# Sheet2.net
KiCad netlist of a schematic drawn in Altium Designer
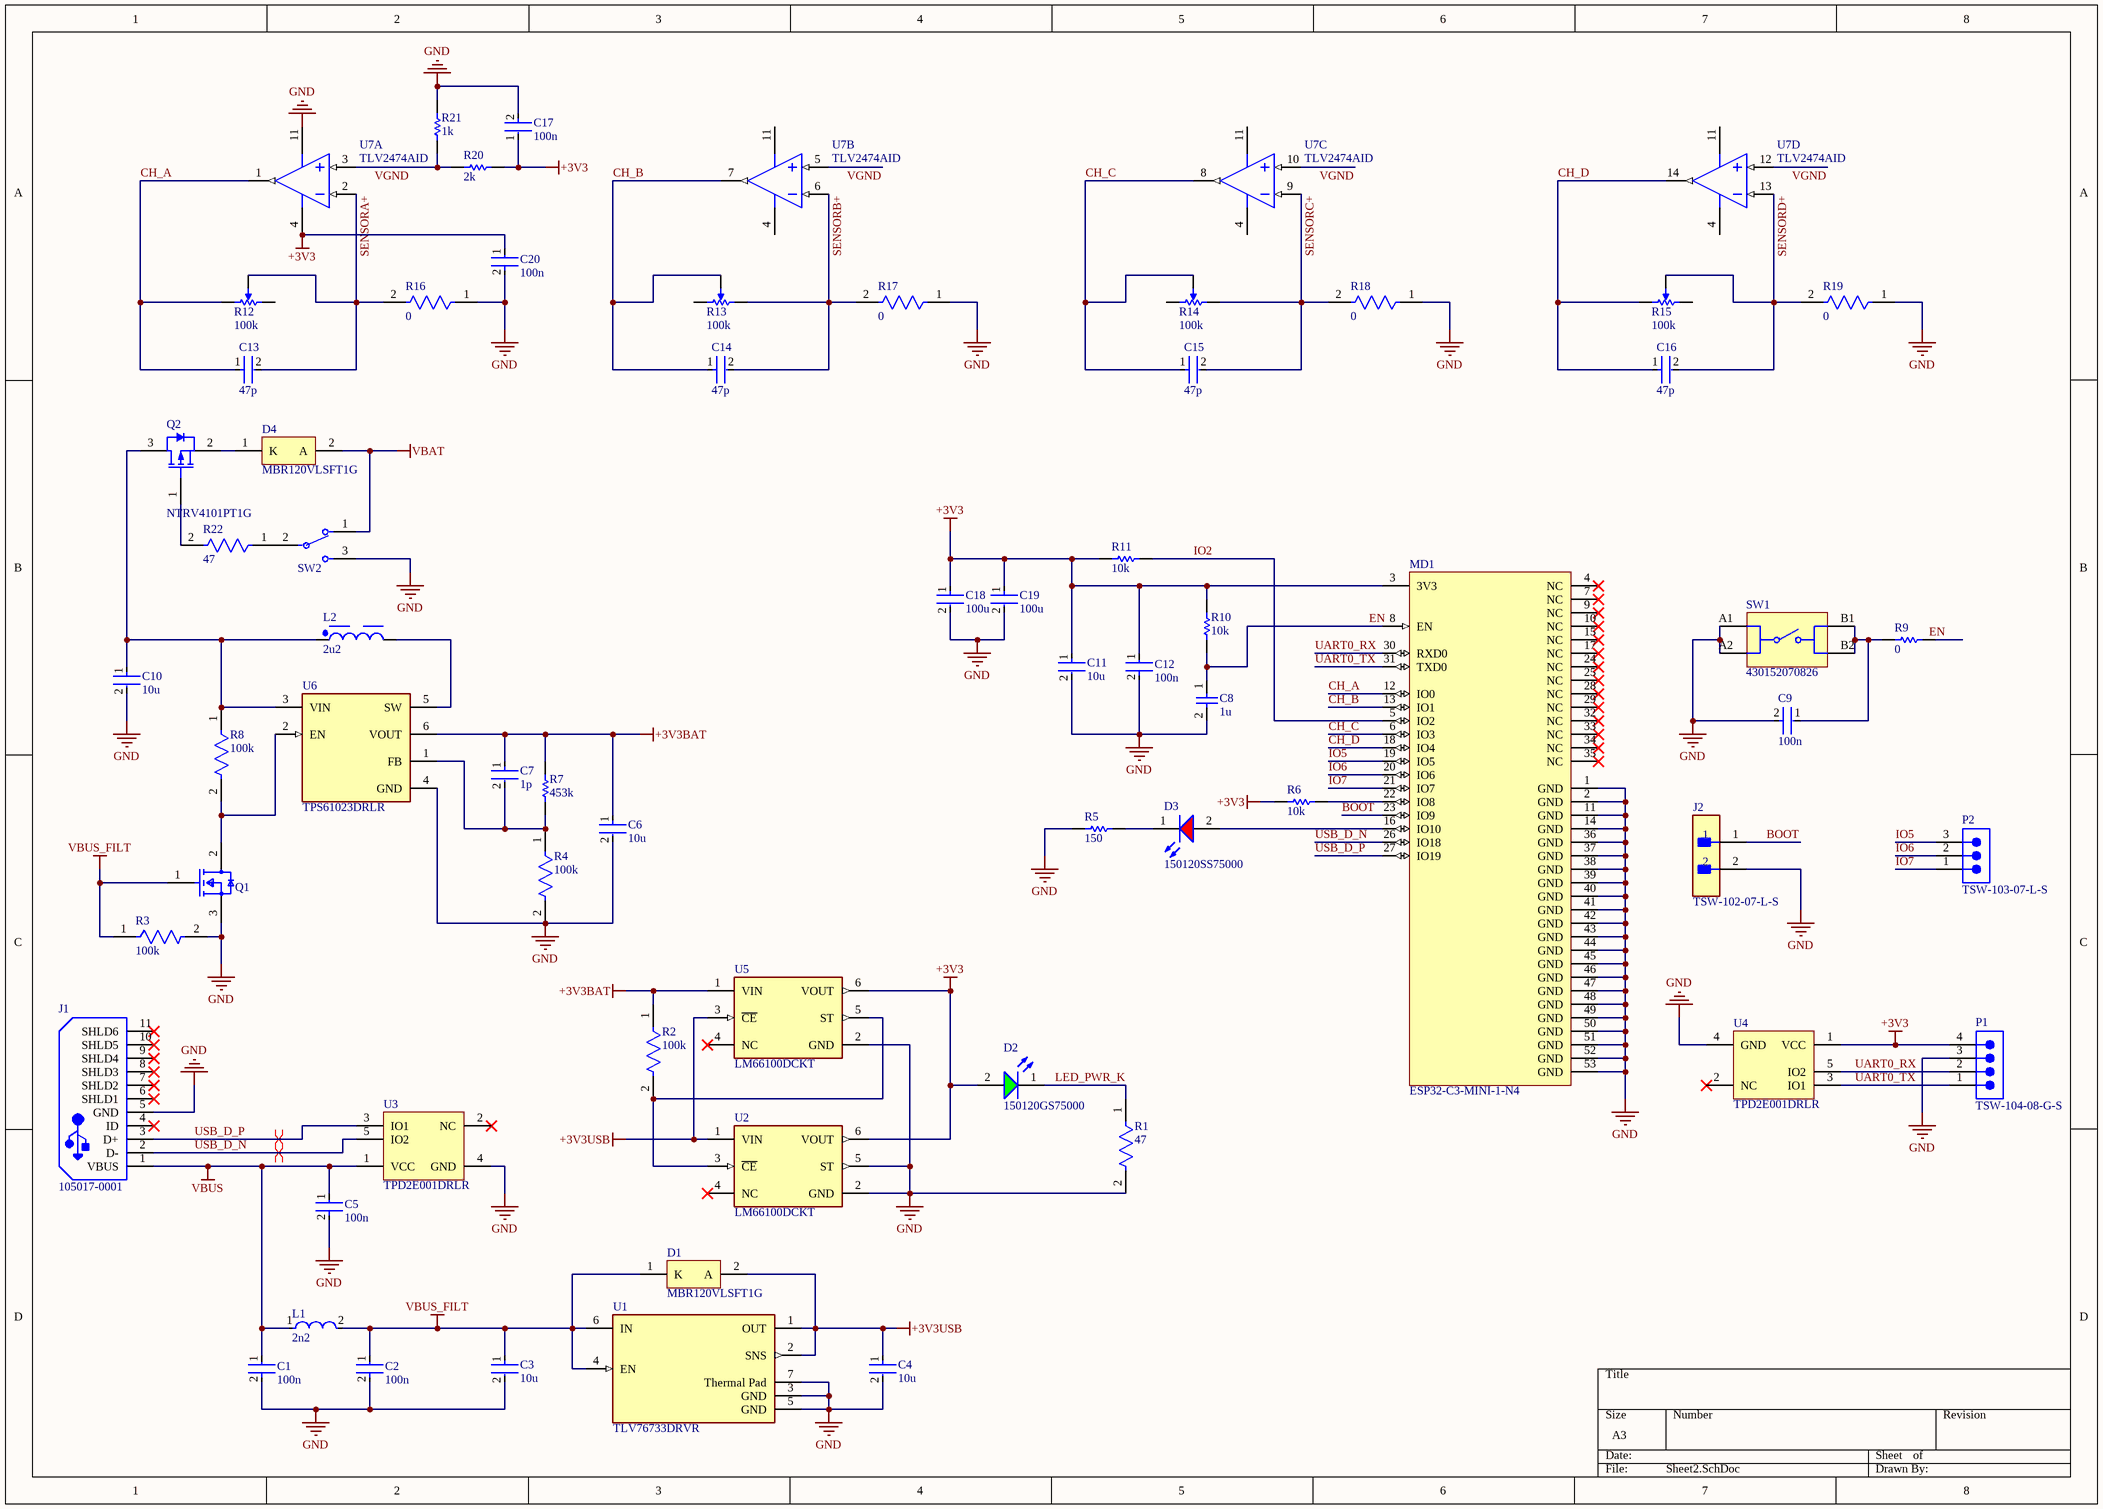
[diagram p0: Sheet2.SchDoc]

(export (version "E")
  (design (tool "Eeschema 10.0.6"))
  (components
    (comp (ref "C1")
      (value "100n")
      (footprint "FP-GRM15-MFG")
      (description "CAP CER 0.1UF 16V X7R 0402")
      (fields (field (name "MANUFACTURER PART NUMBER") "GRM155R71C104KA88D") (field (name "TOLERANCE") "10%"))
      (libsource (lib "Altium Content Vault") (part "236180d848d6139a670b325ea6854c9"))
    )
    (comp (ref "C2")
      (value "100n")
      (footprint "FP-GRM15-MFG")
      (description "CAP CER 0.1UF 16V X7R 0402")
      (fields (field (name "MANUFACTURER PART NUMBER") "GRM155R71C104KA88D") (field (name "TOLERANCE") "10%"))
      (libsource (lib "Altium Content Vault") (part "236180d848d6139a670b325ea6854c9"))
    )
    (comp (ref "C3")
      (value "10u")
      (footprint "FP-CL21-IPC_C")
      (description "CL21 Series 0805 10uF 10V ±20% Tolerance X5R Multilayer Ceramic Chip Capacitor")
      (fields (field (name "TOLERANCE") "20%"))
      (libsource (lib "Altium Content Vault") (part "b4654b650e69147ec39a6b967a45e02"))
    )
    (comp (ref "C4")
      (value "10u")
      (footprint "FP-CL21-IPC_C")
      (description "CL21 Series 0805 10uF 10V ±20% Tolerance X5R Multilayer Ceramic Chip Capacitor")
      (fields (field (name "TOLERANCE") "20%"))
      (libsource (lib "Altium Content Vault") (part "b4654b650e69147ec39a6b967a45e02"))
    )
    (comp (ref "C5")
      (value "100n")
      (footprint "FP-GRM15-MFG")
      (description "CAP CER 0.1UF 16V X7R 0402")
      (fields (field (name "MANUFACTURER PART NUMBER") "GRM155R71C104KA88D") (field (name "TOLERANCE") "10%"))
      (libsource (lib "Altium Content Vault") (part "236180d848d6139a670b325ea6854c9"))
    )
    (comp (ref "C6")
      (value "10u")
      (footprint "FP-CL21-IPC_C")
      (description "CL21 Series 0805 10uF 10V ±20% Tolerance X5R Multilayer Ceramic Chip Capacitor")
      (fields (field (name "TOLERANCE") "20%"))
      (libsource (lib "Altium Content Vault") (part "b4654b650e69147ec39a6b967a45e02"))
    )
    (comp (ref "C7")
      (value "1p")
      (footprint "FP-GJM155-0_05-IPC_B")
      (description "Multi-Layer Ceramic Capacitor 1pF C0G  ±0.1pF 0402 Paper T/R")
      (fields (field (name "VOLTAGE") "50V"))
      (libsource (lib "Altium Content Vault") (part "02cd4be3c70576c341d710602a673aa"))
    )
    (comp (ref "C8")
      (value "1u")
      (footprint "CAPC2013X135X45LL10T25")
      (fields (field (name "MANUFACTURER") "Murata") (field (name "PART NUMBER") "GRM21BR71C105KA01K"))
      (libsource (lib "Altium Content Vault") (part "CAP"))
    )
    (comp (ref "C9")
      (value "100n")
      (footprint "FP-GRM15-MFG")
      (description "CAP CER 0.1UF 16V X7R 0402")
      (fields (field (name "MANUFACTURER PART NUMBER") "GRM155R71C104KA88D") (field (name "TOLERANCE") "10%"))
      (libsource (lib "Altium Content Vault") (part "236180d848d6139a670b325ea6854c9"))
    )
    (comp (ref "C10")
      (value "10u")
      (footprint "FP-GRM21B-0_1-IPC_C")
      (description "Chip Multilayer Ceramic Capacitors for General Purpose, 0805, 10uF, X5R, 15%, 10%, 16V")
      (fields (field (name "TOLERANCE") "10%") (field (name "VOLTAGE") "16V"))
      (libsource (lib "Altium Content Vault") (part "b4654b650e69147ec39a6b967a45e02"))
    )
    (comp (ref "C11")
      (value "10u")
      (footprint "FP-GRM21B-0_1-IPC_C")
      (description "Chip Multilayer Ceramic Capacitors for General Purpose, 0805, 10uF, X5R, 15%, 10%, 16V")
      (fields (field (name "TOLERANCE") "10%") (field (name "VOLTAGE") "16V"))
      (libsource (lib "Altium Content Vault") (part "b4654b650e69147ec39a6b967a45e02"))
    )
    (comp (ref "C12")
      (value "100n")
      (footprint "FP-GRM15-MFG")
      (description "CAP CER 0.1UF 16V X7R 0402")
      (fields (field (name "MANUFACTURER PART NUMBER") "GRM155R71C104KA88D") (field (name "TOLERANCE") "10%"))
      (libsource (lib "Altium Content Vault") (part "236180d848d6139a670b325ea6854c9"))
    )
    (comp (ref "C13")
      (value "47p")
      (footprint "FP-C0805C-DN-MFG")
      (description "CAP CER 47PF 50V C0G/NP0 0805")
      (fields
        (field (name "MANUFACTURER") "KEMET")
        (field (name "MANUFACTURER PART NUMBER") "C0805C470J5GACTU")
      )
      (libsource (lib "Altium Content Vault") (part "b4654b650e69147ec39a6b967a45e02"))
    )
    (comp (ref "C14")
      (value "47p")
      (footprint "FP-C0805C-DN-MFG")
      (description "CAP CER 47PF 50V C0G/NP0 0805")
      (fields
        (field (name "MANUFACTURER") "KEMET")
        (field (name "MANUFACTURER PART NUMBER") "C0805C470J5GACTU")
      )
      (libsource (lib "Altium Content Vault") (part "b4654b650e69147ec39a6b967a45e02"))
    )
    (comp (ref "C15")
      (value "47p")
      (footprint "FP-C0805C-DN-MFG")
      (description "CAP CER 47PF 50V C0G/NP0 0805")
      (fields
        (field (name "MANUFACTURER") "KEMET")
        (field (name "MANUFACTURER PART NUMBER") "C0805C470J5GACTU")
      )
      (libsource (lib "Altium Content Vault") (part "b4654b650e69147ec39a6b967a45e02"))
    )
    (comp (ref "C16")
      (value "47p")
      (footprint "FP-C0805C-DN-MFG")
      (description "CAP CER 47PF 50V C0G/NP0 0805")
      (fields
        (field (name "MANUFACTURER") "KEMET")
        (field (name "MANUFACTURER PART NUMBER") "C0805C470J5GACTU")
      )
      (libsource (lib "Altium Content Vault") (part "b4654b650e69147ec39a6b967a45e02"))
    )
    (comp (ref "C17")
      (value "100n")
      (footprint "FP-GRM15-MFG")
      (description "CAP CER 0.1UF 16V X7R 0402")
      (fields (field (name "MANUFACTURER PART NUMBER") "GRM155R71C104KA88D") (field (name "TOLERANCE") "10%"))
      (libsource (lib "Altium Content Vault") (part "236180d848d6139a670b325ea6854c9"))
    )
    (comp (ref "C18")
      (value "100u")
      (footprint "FP-CL32-IPC_C")
      (description "Cap Ceramic 100uF 10V X5R ±20% SMD 1210 +85°C Embossed T/R")
      (fields (field (name "VOLTAGE") "10V") (field (name "TOLERANCE") "20%"))
      (libsource (lib "Altium Content Vault") (part "b4654b650e69147ec39a6b967a45e02"))
    )
    (comp (ref "C19")
      (value "100u")
      (footprint "FP-CL32-IPC_C")
      (description "Cap Ceramic 100uF 10V X5R ±20% SMD 1210 +85°C Embossed T/R")
      (fields (field (name "VOLTAGE") "10V") (field (name "TOLERANCE") "20%"))
      (libsource (lib "Altium Content Vault") (part "b4654b650e69147ec39a6b967a45e02"))
    )
    (comp (ref "C20")
      (value "100n")
      (footprint "FP-GRM15-MFG")
      (description "CAP CER 0.1UF 16V X7R 0402")
      (fields (field (name "MANUFACTURER PART NUMBER") "GRM155R71C104KA88D") (field (name "TOLERANCE") "10%"))
      (libsource (lib "Altium Content Vault") (part "236180d848d6139a670b325ea6854c9"))
    )
    (comp (ref "D1")
      (value "MBR120VLSFT1G")
      (footprint "ONSC-SOD-123FL-2-498-01_V")
      (description "Schottky Power Rectifier, 2-Pin SOD-123, Pb-Free, Tape and Reel")
      (fields (field (name "MANUFACTURER") "On Semiconductor"))
      (libsource (lib "Altium Content Vault") (part "ONSC-D-K1A2-2_A"))
    )
    (comp (ref "D2")
      (value "150120GS75000")
      (footprint "WL-SMCW_1206_150120xx75000")
      (description "WL-SMCW SMT Mono-Color Chip LED Waterclear")
      (libsource (lib "Altium Content Vault") (part "LED_Green_2A-1K"))
    )
    (comp (ref "D3")
      (value "150120SS75000")
      (footprint "WL-SMCW_1206_150120xx75000")
      (description "Led, Red, 630 Nm, 1.9 V, 30 Ma, 60 Mcd Rohs Compliant: Yes")
      (libsource (lib "Altium Content Vault") (part "LED_Red_2A-1K"))
    )
    (comp (ref "D4")
      (value "MBR120VLSFT1G")
      (footprint "ONSC-SOD-123FL-2-498-01_V")
      (description "Schottky Power Rectifier, 2-Pin SOD-123, Pb-Free, Tape and Reel")
      (fields (field (name "MANUFACTURER") "On Semiconductor"))
      (libsource (lib "Altium Content Vault") (part "ONSC-D-K1A2-2_A"))
    )
    (comp (ref "J1")
      (value "105017-0001")
      (footprint "USB-MICRO-B_V")
      (fields (field (name "MANUFACTURER") "Molex"))
      (libsource (lib "Altium Content Vault") (part "USB-5-6SHLD"))
    )
    (comp (ref "J2")
      (value "TSW-102-07-L-S")
      (footprint "FP-TSW-102-07-L-S-MFG")
      (description "CONN HEADER VERT 2POS 2.54MM")
      (libsource (lib "Altium Content Vault") (part "3bc925449376181038e59eaffc5286c"))
    )
    (comp (ref "L1")
      (value "2n2")
      (footprint "FP-LQW15AN_80-MFG")
      (description "Wire Wound RF Inductor 2.2nH ±0.1nH 2530mA 0.022Ω 0402 (1005)")
      (libsource (lib "Altium Content Vault") (part "725321dda6339637d4d059423bc1c3c"))
    )
    (comp (ref "L2")
      (value "2u2")
      (footprint "WE-PD_7332R")
      (fields (field (name "TOLERANCE") "20%"))
      (libsource (lib "Altium Content Vault") (part "Inductor - 2"))
    )
    (comp (ref "MD1")
      (value "ESP32-C3-MINI-1-N4")
      (footprint "FP-ESP32-C3-MINI-1-N4-MFG")
      (description "Multiprotocol Modules SMD module, ESP32-C3FN4, PCB antenna, -40 C +85 C")
      (libsource (lib "Altium Content Vault") (part "ESP32-C3-MINI-1-N4"))
    )
    (comp (ref "P1")
      (value "TSW-104-08-G-S")
      (footprint "SMTC-TSW-104-08-X-S")
      (description "0.025\" SQ Post Header, Through-hole, Vertical, -55 to 125 degC, 2.54 mm Pitch, 4-Pin, Male, RoHS")
      (fields (field (name "MANUFACTURER") "Samtec"))
      (libsource (lib "Altium Content Vault") (part "SMTC-TSW-104-08-X-S"))
    )
    (comp (ref "P2")
      (value "TSW-103-07-L-S")
      (footprint "SMTC-TSW-103-07-X-S")
      (description "0.025\" SQ Post Header, Through-hole, Vertical, -55 to 125 degC, 2.54 mm Pitch, 3-Pin, Male, RoHS")
      (fields (field (name "MANUFACTURER") "Samtec"))
      (libsource (lib "Altium Content Vault") (part "SMTC-TSW-103-X-X-S-X"))
    )
    (comp (ref "Q1")
      (value "FDN337N")
      (footprint "FP-527AG-MFG")
      (description "MOSFET N-CH 30V 2.2A SSOT3")
      (libsource (lib "Altium Content Vault") (part "b44c8776e10362b01251f5cff19d373"))
    )
    (comp (ref "Q2")
      (value "NTRV4101PT1G")
      (footprint "ONSC-SOT-23-3-318-08_V")
      (description "Trench Power MOSFET, -20 V, Single P-Channel, 3-Pin SOT-23, Pb-Free, Tape and Reel")
      (fields (field (name "MANUFACTURER") "On Semiconductor"))
      (libsource (lib "Altium Content Vault") (part "ONSC-PMOS-G1S2D3-3_D"))
    )
    (comp (ref "R1")
      (value "47")
      (footprint "FP-RC0603-0_55-MFG")
      (fields (field (name "TOLERANCE") "1%"))
      (libsource (lib "Altium Content Vault") (part "1029c3af85768c4190bb7ad29bc67b5"))
    )
    (comp (ref "R2")
      (value "100k")
      (footprint "FP-RC0805-0_6-IPC_C")
      (description "RES 100K OHM 1% 1/8W 0805")
      (fields (field (name "TOLERANCE") "1%"))
      (libsource (lib "Altium Content Vault") (part "1029c3af85768c4190bb7ad29bc67b5"))
    )
    (comp (ref "R3")
      (value "100k")
      (footprint "FP-RC0805-0_6-IPC_C")
      (description "RES 100K OHM 1% 1/8W 0805")
      (fields (field (name "TOLERANCE") "1%"))
      (libsource (lib "Altium Content Vault") (part "1029c3af85768c4190bb7ad29bc67b5"))
    )
    (comp (ref "R4")
      (value "100k")
      (footprint "FP-RC0805-0_6-IPC_C")
      (description "RES 100K OHM 1% 1/8W 0805")
      (fields (field (name "TOLERANCE") "1%"))
      (libsource (lib "Altium Content Vault") (part "1029c3af85768c4190bb7ad29bc67b5"))
    )
    (comp (ref "R5")
      (value "150")
      (footprint "RESC1608X55X25ML10T15")
      (description "Chip Resistor, 150 Ohm, +/- 1%, 0.1 W, -55 to 155 degC, 0603 (1608 Metric), RoHS, Tape and Reel")
      (libsource (lib "Altium Content Vault") (part "RES-2"))
    )
    (comp (ref "R6")
      (value "10k")
      (footprint "RESC2013X60X35NL10T20")
      (description "Chip Resistor, 10 KOhm, +/- 1%, 0.125 W, -55 to 155 degC, 0805 (2012 Metric), RoHS, Tape and Reel")
      (fields (field (name "MANUFACTURER") "Yageo"))
      (libsource (lib "Altium Content Vault") (part "RES-2"))
    )
    (comp (ref "R7")
      (value "453k")
      (footprint "RESC2013X60X35NL10T20")
      (fields (field (name "PART NUMBER") "RC0805FR-07453KL") (field (name "MANUFACTURER") "Yageo"))
      (libsource (lib "Altium Content Vault") (part "RES"))
    )
    (comp (ref "R8")
      (value "100k")
      (footprint "FP-RC0805-0_6-IPC_C")
      (description "RES 100K OHM 1% 1/8W 0805")
      (fields (field (name "TOLERANCE") "1%"))
      (libsource (lib "Altium Content Vault") (part "1029c3af85768c4190bb7ad29bc67b5"))
    )
    (comp (ref "R9")
      (value "0")
      (footprint "RESC2013X60X35ML10T20")
      (fields (field (name "TOLERANCE") "5%") (field (name "MANUFACTURER") "Yageo"))
      (libsource (lib "Altium Content Vault") (part "RES-2"))
    )
    (comp (ref "R10")
      (value "10k")
      (footprint "RESC2013X60X35NL10T20")
      (description "Chip Resistor, 10 KOhm, +/- 1%, 0.125 W, -55 to 155 degC, 0805 (2012 Metric), RoHS, Tape and Reel")
      (fields (field (name "MANUFACTURER") "Yageo"))
      (libsource (lib "Altium Content Vault") (part "RES-2"))
    )
    (comp (ref "R11")
      (value "10k")
      (footprint "RESC2013X60X35NL10T20")
      (description "Chip Resistor, 10 KOhm, +/- 1%, 0.125 W, -55 to 155 degC, 0805 (2012 Metric), RoHS, Tape and Reel")
      (fields (field (name "MANUFACTURER") "Yageo"))
      (libsource (lib "Altium Content Vault") (part "RES-2"))
    )
    (comp (ref "R12")
      (value "100k")
      (footprint "BOUR-3214W_V")
      (fields (field (name "MANUFACTURER") "Bourns"))
      (libsource (lib "Altium Content Vault") (part "RES-ADJ-3_A"))
    )
    (comp (ref "R13")
      (value "100k")
      (footprint "BOUR-3214W_V")
      (fields (field (name "MANUFACTURER") "Bourns"))
      (libsource (lib "Altium Content Vault") (part "RES-ADJ-3_A"))
    )
    (comp (ref "R14")
      (value "100k")
      (footprint "BOUR-3214W_V")
      (fields (field (name "MANUFACTURER") "Bourns"))
      (libsource (lib "Altium Content Vault") (part "RES-ADJ-3_A"))
    )
    (comp (ref "R15")
      (value "100k")
      (footprint "BOUR-3214W_V")
      (fields (field (name "MANUFACTURER") "Bourns"))
      (libsource (lib "Altium Content Vault") (part "RES-ADJ-3_A"))
    )
    (comp (ref "R16")
      (value "0")
      (footprint "FP-RC2512-0_65-IPC_C")
      (description "RES SMD 0 OHM JUMPER 1W 2512")
      (fields (field (name "TOLERANCE") "5%"))
      (libsource (lib "Altium Content Vault") (part "1029c3af85768c4190bb7ad29bc67b5"))
    )
    (comp (ref "R17")
      (value "0")
      (footprint "FP-RC2512-0_65-IPC_C")
      (description "RES SMD 0 OHM JUMPER 1W 2512")
      (fields (field (name "TOLERANCE") "5%"))
      (libsource (lib "Altium Content Vault") (part "1029c3af85768c4190bb7ad29bc67b5"))
    )
    (comp (ref "R18")
      (value "0")
      (footprint "FP-RC2512-0_65-IPC_C")
      (description "RES SMD 0 OHM JUMPER 1W 2512")
      (fields (field (name "TOLERANCE") "5%"))
      (libsource (lib "Altium Content Vault") (part "1029c3af85768c4190bb7ad29bc67b5"))
    )
    (comp (ref "R19")
      (value "0")
      (footprint "FP-RC2512-0_65-IPC_C")
      (description "RES SMD 0 OHM JUMPER 1W 2512")
      (fields (field (name "TOLERANCE") "5%"))
      (libsource (lib "Altium Content Vault") (part "1029c3af85768c4190bb7ad29bc67b5"))
    )
    (comp (ref "R20")
      (value "2k")
      (footprint "RESC2013X60X35ML10T20")
      (fields (field (name "MANUFACTURER") "Yageo") (field (name "PART NUMBER") "RC0805JR-072KL"))
      (libsource (lib "Altium Content Vault") (part "RES"))
    )
    (comp (ref "R21")
      (value "1k")
      (footprint "RESC2013X60X35ML10T20")
      (description "Chip Resistor, 1 KOhm, +/- 1%, 125 mW, -55 to 155 degC, 0805 (2012 Metric), RoHS, Tape and Reel")
      (fields (field (name "TOLERANCE") "1%") (field (name "MANUFACTURER") "Yageo"))
      (libsource (lib "Altium Content Vault") (part "RES-2"))
    )
    (comp (ref "R22")
      (value "47")
      (footprint "FP-RC0603-0_55-MFG")
      (fields (field (name "TOLERANCE") "1%"))
      (libsource (lib "Altium Content Vault") (part "1029c3af85768c4190bb7ad29bc67b5"))
    )
    (comp (ref "SW1")
      (value "430152070826")
      (footprint "430152070826")
      (description "Switch Tactile N.O. SPST Round Button Gull Wing 0.05A 12VDC 500000Cycles 2.55N SMD Reel")
      (libsource (lib "Altium Content Vault") (part "SPST-NO_4P"))
    )
    (comp (ref "SW2")
      (value "JS102011SAQN")
      (footprint "FP-JS102011SAQN-MFG")
      (description "SWITCH SLIDE SPDT 300MA 6V")
      (libsource (lib "Altium Content Vault") (part "39e195cbbadc85d1df0d7eb6847d379"))
    )
    (comp (ref "U1")
      (value "TLV76733DRVR")
      (footprint "FP-DRV0006A-IPC_C")
      (description "VOLTAGE COMPARATOR")
      (libsource (lib "Altium Content Vault") (part "527f072e48108a7b9f646086bfc5874"))
    )
    (comp (ref "U2")
      (value "LM66100DCKT")
      (footprint "FP-DCK0006A-IPC_C")
      (description "IC OR CTRLR IDEAL DIODE SC70-6")
      (libsource (lib "Altium Content Vault") (part "3595dc506fef48fc1df3095330a4feb"))
    )
    (comp (ref "U3")
      (value "TPD2E001DRLR")
      (footprint "DRL0005A_L")
      (fields (field (name "MANUFACTURER") "Texas Instruments"))
      (libsource (lib "") (part "TI-TPD2E001-SOT_DRL-5_1"))
    )
    (comp (ref "U4")
      (value "TPD2E001DRLR")
      (footprint "DRL0005A_L")
      (fields (field (name "MANUFACTURER") "Texas Instruments"))
      (libsource (lib "Altium Content Vault") (part "TI-TPD2E001-SOT_DRL-5"))
    )
    (comp (ref "U5")
      (value "LM66100DCKT")
      (footprint "FP-DCK0006A-IPC_C")
      (description "IC OR CTRLR IDEAL DIODE SC70-6")
      (libsource (lib "Altium Content Vault") (part "3595dc506fef48fc1df3095330a4feb"))
    )
    (comp (ref "U6")
      (value "TPS61023DRLR")
      (footprint "FP-DRL0006A-MFG")
      (description "FINISH GOODS FOR TPS61023")
      (libsource (lib "Altium Content Vault") (part "b28b3e956a4ad07201ce69f9d09f9a8"))
    )
    (comp (ref "U7")
      (value "TLV2474AID")
      (footprint "D0014A_N")
      (fields (field (name "MANUFACTURER") "Texas Instruments"))
      (libsource (lib "Altium Content Vault") (part "TI-TLC_TLV_TLC1079-14"))
    )
  )
  (nets
    (net (code "1") (name "+3V3") (class "Default")
      (node (ref "C11") (pin "1") (pinfunction "1_1") (pintype "passive"))
      (node (ref "C12") (pin "1") (pinfunction "1_1") (pintype "passive"))
      (node (ref "C17") (pin "1") (pinfunction "1_1") (pintype "passive"))
      (node (ref "C18") (pin "1") (pinfunction "1_1") (pintype "passive"))
      (node (ref "C19") (pin "1") (pinfunction "1_1") (pintype "passive"))
      (node (ref "C20") (pin "1") (pinfunction "1_1") (pintype "passive"))
      (node (ref "D2") (pin "2") (pinfunction "A_2") (pintype "passive"))
      (node (ref "MD1") (pin "3") (pinfunction "3V3_3") (pintype "power_in"))
      (node (ref "P1") (pin "4") (pinfunction "4_4") (pintype "passive"))
      (node (ref "R10") (pin "2") (pinfunction "2_2") (pintype "passive"))
      (node (ref "R11") (pin "1") (pinfunction "1_1") (pintype "passive"))
      (node (ref "R20") (pin "2") (pinfunction "2_2") (pintype "passive"))
      (node (ref "R6") (pin "1") (pinfunction "1_1") (pintype "passive"))
      (node (ref "U2") (pin "6") (pinfunction "VOUT_6") (pintype "output"))
      (node (ref "U4") (pin "1") (pinfunction "VCC_1") (pintype "power_in"))
      (node (ref "U5") (pin "6") (pinfunction "VOUT_6") (pintype "output"))
      (node (ref "U7") (pin "4") (pinfunction "VDD_4") (pintype "power_in"))
    )
    (net (code "2") (name "+3V3BAT") (class "Default")
      (node (ref "C6") (pin "1") (pinfunction "1_1") (pintype "passive"))
      (node (ref "C7") (pin "1") (pinfunction "1_1") (pintype "passive"))
      (node (ref "R2") (pin "1") (pinfunction "1_1") (pintype "passive"))
      (node (ref "R7") (pin "2") (pinfunction "2_2") (pintype "passive"))
      (node (ref "U5") (pin "1") (pinfunction "VIN_1") (pintype "power_in"))
      (node (ref "U6") (pin "6") (pinfunction "VOUT_6") (pintype "power_in"))
    )
    (net (code "3") (name "+3V3USB") (class "Default")
      (node (ref "C4") (pin "1") (pinfunction "1_1") (pintype "passive"))
      (node (ref "D1") (pin "2") (pinfunction "A_2") (pintype "passive"))
      (node (ref "U1") (pin "1") (pinfunction "OUT_1") (pintype "passive"))
      (node (ref "U1") (pin "2") (pinfunction "SNS_2") (pintype "output"))
      (node (ref "U2") (pin "1") (pinfunction "VIN_1") (pintype "power_in"))
      (node (ref "U5") (pin "3") (pinfunction "~{CE}_3") (pintype "input"))
    )
    (net (code "4") (name "/BOOT") (class "Default")
      (node (ref "J2") (pin "1") (pinfunction "1_1") (pintype "passive"))
      (node (ref "MD1") (pin "23") (pinfunction "IO9_23") (pintype "bidirectional"))
    )
    (net (code "5") (name "/CH_A") (class "Default")
      (node (ref "C13") (pin "1") (pinfunction "1_1") (pintype "passive"))
      (node (ref "MD1") (pin "12") (pinfunction "IO0_12") (pintype "bidirectional"))
      (node (ref "R12") (pin "3") (pinfunction "3_3") (pintype "passive"))
      (node (ref "U7") (pin "1") (pinfunction "OUT1_1") (pintype "output"))
    )
    (net (code "6") (name "/CH_B") (class "Default")
      (node (ref "C14") (pin "1") (pinfunction "1_1") (pintype "passive"))
      (node (ref "MD1") (pin "13") (pinfunction "IO1_13") (pintype "bidirectional"))
      (node (ref "R13") (pin "2") (pinfunction "2_2") (pintype "passive"))
      (node (ref "U7") (pin "7") (pinfunction "OUT2_7") (pintype "output"))
    )
    (net (code "7") (name "/CH_C") (class "Default")
      (node (ref "C15") (pin "1") (pinfunction "1_1") (pintype "passive"))
      (node (ref "MD1") (pin "6") (pinfunction "IO3_6") (pintype "bidirectional"))
      (node (ref "R14") (pin "2") (pinfunction "2_2") (pintype "passive"))
      (node (ref "U7") (pin "8") (pinfunction "OUT3_8") (pintype "output"))
    )
    (net (code "8") (name "/CH_D") (class "Default")
      (node (ref "C16") (pin "1") (pinfunction "1_1") (pintype "passive"))
      (node (ref "MD1") (pin "18") (pinfunction "IO4_18") (pintype "bidirectional"))
      (node (ref "R15") (pin "3") (pinfunction "3_3") (pintype "passive"))
      (node (ref "U7") (pin "14") (pinfunction "OUT4_14") (pintype "output"))
    )
    (net (code "9") (name "/EN") (class "Default")
      (node (ref "C8") (pin "1") (pinfunction "1_1") (pintype "passive"))
      (node (ref "MD1") (pin "8") (pinfunction "EN_8") (pintype "input"))
      (node (ref "R10") (pin "1") (pinfunction "1_1") (pintype "passive"))
      (node (ref "R9") (pin "2") (pinfunction "2_2") (pintype "passive"))
    )
    (net (code "10") (name "/IO2") (class "Default")
      (node (ref "MD1") (pin "5") (pinfunction "IO2_5") (pintype "bidirectional"))
      (node (ref "R11") (pin "2") (pinfunction "2_2") (pintype "passive"))
    )
    (net (code "11") (name "/IO5") (class "Default")
      (node (ref "MD1") (pin "19") (pinfunction "IO5_19") (pintype "bidirectional"))
      (node (ref "P2") (pin "3") (pinfunction "3_3") (pintype "passive"))
    )
    (net (code "12") (name "/IO6") (class "Default")
      (node (ref "MD1") (pin "20") (pinfunction "IO6_20") (pintype "bidirectional"))
      (node (ref "P2") (pin "2") (pinfunction "2_2") (pintype "passive"))
    )
    (net (code "13") (name "/IO7") (class "Default")
      (node (ref "MD1") (pin "21") (pinfunction "IO7_21") (pintype "bidirectional"))
      (node (ref "P2") (pin "1") (pinfunction "1_1") (pintype "passive"))
    )
    (net (code "14") (name "/LED_PWR_K") (class "Default")
      (node (ref "D2") (pin "1") (pinfunction "K_1") (pintype "passive"))
      (node (ref "R1") (pin "1") (pinfunction "1_1") (pintype "passive"))
    )
    (net (code "15") (name "/SENSORA+") (class "Default")
      (node (ref "C13") (pin "2") (pinfunction "2_2") (pintype "passive"))
      (node (ref "R12") (pin "2") (pinfunction "2_2") (pintype "passive"))
      (node (ref "R16") (pin "2") (pinfunction "2_2") (pintype "passive"))
      (node (ref "U7") (pin "2") (pinfunction "IN1-_2") (pintype "input"))
    )
    (net (code "16") (name "/SENSORB+") (class "Default")
      (node (ref "C14") (pin "2") (pinfunction "2_2") (pintype "passive"))
      (node (ref "R13") (pin "1") (pinfunction "1_1") (pintype "passive"))
      (node (ref "R17") (pin "2") (pinfunction "2_2") (pintype "passive"))
      (node (ref "U7") (pin "6") (pinfunction "IN2-_6") (pintype "input"))
    )
    (net (code "17") (name "/SENSORC+") (class "Default")
      (node (ref "C15") (pin "2") (pinfunction "2_2") (pintype "passive"))
      (node (ref "R14") (pin "1") (pinfunction "1_1") (pintype "passive"))
      (node (ref "R18") (pin "2") (pinfunction "2_2") (pintype "passive"))
      (node (ref "U7") (pin "9") (pinfunction "IN3-_9") (pintype "input"))
    )
    (net (code "18") (name "/SENSORD+") (class "Default")
      (node (ref "C16") (pin "2") (pinfunction "2_2") (pintype "passive"))
      (node (ref "R15") (pin "2") (pinfunction "2_2") (pintype "passive"))
      (node (ref "R19") (pin "2") (pinfunction "2_2") (pintype "passive"))
      (node (ref "U7") (pin "13") (pinfunction "IN4-_13") (pintype "input"))
    )
    (net (code "19") (name "/UART0_RX") (class "Default")
      (node (ref "MD1") (pin "30") (pinfunction "RXD0_30") (pintype "bidirectional"))
      (node (ref "P1") (pin "2") (pinfunction "2_2") (pintype "passive"))
      (node (ref "U4") (pin "5") (pinfunction "IO2_5") (pintype "passive"))
    )
    (net (code "20") (name "/UART0_TX") (class "Default")
      (node (ref "MD1") (pin "31") (pinfunction "TXD0_31") (pintype "bidirectional"))
      (node (ref "P1") (pin "1") (pinfunction "1_1") (pintype "passive"))
      (node (ref "U4") (pin "3") (pinfunction "IO1_3") (pintype "passive"))
    )
    (net (code "21") (name "/USB_D_N") (class "Default")
      (node (ref "J1") (pin "2") (pinfunction "D-_2") (pintype "passive"))
      (node (ref "MD1") (pin "26") (pinfunction "IO18_26") (pintype "bidirectional"))
      (node (ref "U3") (pin "5") (pinfunction "IO2_5") (pintype "passive"))
    )
    (net (code "22") (name "/USB_D_P") (class "Default")
      (node (ref "J1") (pin "3") (pinfunction "D+_3") (pintype "passive"))
      (node (ref "MD1") (pin "27") (pinfunction "IO19_27") (pintype "bidirectional"))
      (node (ref "U3") (pin "3") (pinfunction "IO1_3") (pintype "passive"))
    )
    (net (code "23") (name "/VGND") (class "Default")
      (node (ref "R20") (pin "1") (pinfunction "1_1") (pintype "passive"))
      (node (ref "R21") (pin "1") (pinfunction "1_1") (pintype "passive"))
      (node (ref "U7") (pin "10") (pinfunction "IN3+_10") (pintype "input"))
      (node (ref "U7") (pin "12") (pinfunction "IN4+_12") (pintype "input"))
      (node (ref "U7") (pin "3") (pinfunction "IN1+_3") (pintype "input"))
      (node (ref "U7") (pin "5") (pinfunction "IN2+_5") (pintype "input"))
    )
    (net (code "24") (name "GND") (class "Default")
      (node (ref "C1") (pin "2") (pinfunction "2_2") (pintype "passive"))
      (node (ref "C10") (pin "2") (pinfunction "2_2") (pintype "passive"))
      (node (ref "C11") (pin "2") (pinfunction "2_2") (pintype "passive"))
      (node (ref "C12") (pin "2") (pinfunction "2_2") (pintype "passive"))
      (node (ref "C17") (pin "2") (pinfunction "2_2") (pintype "passive"))
      (node (ref "C18") (pin "2") (pinfunction "2_2") (pintype "passive"))
      (node (ref "C19") (pin "2") (pinfunction "2_2") (pintype "passive"))
      (node (ref "C2") (pin "2") (pinfunction "2_2") (pintype "passive"))
      (node (ref "C20") (pin "2") (pinfunction "2_2") (pintype "passive"))
      (node (ref "C3") (pin "2") (pinfunction "2_2") (pintype "passive"))
      (node (ref "C4") (pin "2") (pinfunction "2_2") (pintype "passive"))
      (node (ref "C5") (pin "2") (pinfunction "2_2") (pintype "passive"))
      (node (ref "C6") (pin "2") (pinfunction "2_2") (pintype "passive"))
      (node (ref "C8") (pin "2") (pinfunction "2_2") (pintype "passive"))
      (node (ref "C9") (pin "2") (pinfunction "2_2") (pintype "passive"))
      (node (ref "J1") (pin "5") (pinfunction "GND_5") (pintype "passive"))
      (node (ref "J2") (pin "2") (pinfunction "2_2") (pintype "passive"))
      (node (ref "MD1") (pin "1") (pinfunction "GND_1") (pintype "power_in"))
      (node (ref "MD1") (pin "11") (pinfunction "GND_11") (pintype "power_in"))
      (node (ref "MD1") (pin "14") (pinfunction "GND_14") (pintype "power_in"))
      (node (ref "MD1") (pin "2") (pinfunction "GND_2") (pintype "power_in"))
      (node (ref "MD1") (pin "36") (pinfunction "GND_36") (pintype "power_in"))
      (node (ref "MD1") (pin "37") (pinfunction "GND_37") (pintype "power_in"))
      (node (ref "MD1") (pin "38") (pinfunction "GND_38") (pintype "power_in"))
      (node (ref "MD1") (pin "39") (pinfunction "GND_39") (pintype "power_in"))
      (node (ref "MD1") (pin "40") (pinfunction "GND_40") (pintype "power_in"))
      (node (ref "MD1") (pin "41") (pinfunction "GND_41") (pintype "power_in"))
      (node (ref "MD1") (pin "42") (pinfunction "GND_42") (pintype "power_in"))
      (node (ref "MD1") (pin "43") (pinfunction "GND_43") (pintype "power_in"))
      (node (ref "MD1") (pin "44") (pinfunction "GND_44") (pintype "power_in"))
      (node (ref "MD1") (pin "45") (pinfunction "GND_45") (pintype "power_in"))
      (node (ref "MD1") (pin "46") (pinfunction "GND_46") (pintype "power_in"))
      (node (ref "MD1") (pin "47") (pinfunction "GND_47") (pintype "power_in"))
      (node (ref "MD1") (pin "48") (pinfunction "GND_48") (pintype "power_in"))
      (node (ref "MD1") (pin "49") (pinfunction "GND_49") (pintype "power_in"))
      (node (ref "MD1") (pin "50") (pinfunction "GND_50") (pintype "power_in"))
      (node (ref "MD1") (pin "51") (pinfunction "GND_51") (pintype "power_in"))
      (node (ref "MD1") (pin "52") (pinfunction "GND_52") (pintype "power_in"))
      (node (ref "MD1") (pin "53") (pinfunction "GND_53") (pintype "power_in"))
      (node (ref "P1") (pin "3") (pinfunction "3_3") (pintype "passive"))
      (node (ref "Q1") (pin "3") (pinfunction "S_3") (pintype "passive"))
      (node (ref "R1") (pin "2") (pinfunction "2_2") (pintype "passive"))
      (node (ref "R16") (pin "1") (pinfunction "1_1") (pintype "passive"))
      (node (ref "R17") (pin "1") (pinfunction "1_1") (pintype "passive"))
      (node (ref "R18") (pin "1") (pinfunction "1_1") (pintype "passive"))
      (node (ref "R19") (pin "1") (pinfunction "1_1") (pintype "passive"))
      (node (ref "R21") (pin "2") (pinfunction "2_2") (pintype "passive"))
      (node (ref "R3") (pin "2") (pinfunction "2_2") (pintype "passive"))
      (node (ref "R4") (pin "2") (pinfunction "2_2") (pintype "passive"))
      (node (ref "R5") (pin "1") (pinfunction "1_1") (pintype "passive"))
      (node (ref "SW1") (pin "A1") (pinfunction "A1_A1") (pintype "passive"))
      (node (ref "SW1") (pin "A2") (pinfunction "A2_A2") (pintype "passive"))
      (node (ref "SW2") (pin "3") (pinfunction "3_3") (pintype "passive"))
      (node (ref "U1") (pin "3") (pinfunction "GND_3") (pintype "power_in"))
      (node (ref "U1") (pin "5") (pinfunction "GND_5") (pintype "power_in"))
      (node (ref "U1") (pin "7") (pinfunction "Thermal_Pad_7") (pintype "passive"))
      (node (ref "U2") (pin "2") (pinfunction "GND_2") (pintype "power_in"))
      (node (ref "U2") (pin "5") (pinfunction "ST_5") (pintype "output"))
      (node (ref "U3") (pin "4") (pinfunction "GND_4") (pintype "power_in"))
      (node (ref "U4") (pin "4") (pinfunction "GND_4") (pintype "power_in"))
      (node (ref "U5") (pin "2") (pinfunction "GND_2") (pintype "power_in"))
      (node (ref "U6") (pin "4") (pinfunction "GND_4") (pintype "power_in"))
      (node (ref "U7") (pin "11") (pinfunction "GND_11") (pintype "power_in"))
    )
    (net (code "25") (name "Net-(C9-Pad1)") (class "Default")
      (node (ref "C9") (pin "1") (pinfunction "1_1") (pintype "passive"))
      (node (ref "R9") (pin "1") (pinfunction "1_1") (pintype "passive"))
      (node (ref "SW1") (pin "B1") (pinfunction "B1_B1") (pintype "passive"))
      (node (ref "SW1") (pin "B2") (pinfunction "B2_B2") (pintype "passive"))
    )
    (net (code "26") (name "Net-(D3-A)") (class "Default")
      (node (ref "D3") (pin "2") (pinfunction "A_2") (pintype "passive"))
      (node (ref "MD1") (pin "16") (pinfunction "IO10_16") (pintype "bidirectional"))
    )
    (net (code "27") (name "Net-(D3-K)") (class "Default")
      (node (ref "D3") (pin "1") (pinfunction "K_1") (pintype "passive"))
      (node (ref "R5") (pin "2") (pinfunction "2_2") (pintype "passive"))
    )
    (net (code "28") (name "Net-(D4-K)") (class "Default")
      (node (ref "D4") (pin "1") (pinfunction "K_1") (pintype "passive"))
      (node (ref "Q2") (pin "2") (pinfunction "S_2") (pintype "passive"))
    )
    (net (code "29") (name "Net-(MD1-IO8)") (class "Default")
      (node (ref "MD1") (pin "22") (pinfunction "IO8_22") (pintype "bidirectional"))
      (node (ref "R6") (pin "2") (pinfunction "2_2") (pintype "passive"))
    )
    (net (code "30") (name "Net-(Q1-D)") (class "Default")
      (node (ref "Q1") (pin "2") (pinfunction "D_2") (pintype "passive"))
      (node (ref "R8") (pin "2") (pinfunction "2_2") (pintype "passive"))
      (node (ref "U6") (pin "2") (pinfunction "EN_2") (pintype "input"))
    )
    (net (code "31") (name "Net-(Q2-D)") (class "Default")
      (node (ref "C10") (pin "1") (pinfunction "1_1") (pintype "passive"))
      (node (ref "L2") (pin "1") (pinfunction "1_1") (pintype "passive"))
      (node (ref "Q2") (pin "3") (pinfunction "D_3") (pintype "passive"))
      (node (ref "R8") (pin "1") (pinfunction "1_1") (pintype "passive"))
      (node (ref "U6") (pin "3") (pinfunction "VIN_3") (pintype "power_in"))
    )
    (net (code "32") (name "Net-(Q2-G)") (class "Default")
      (node (ref "Q2") (pin "1") (pinfunction "G_1") (pintype "passive"))
      (node (ref "R22") (pin "2") (pinfunction "2_2") (pintype "passive"))
    )
    (net (code "33") (name "Net-(SW2-C)") (class "Default")
      (node (ref "R22") (pin "1") (pinfunction "1_1") (pintype "passive"))
      (node (ref "SW2") (pin "2") (pinfunction "C_2") (pintype "passive"))
    )
    (net (code "34") (name "Net-(U2-~{CE})") (class "Default")
      (node (ref "R2") (pin "2") (pinfunction "2_2") (pintype "passive"))
      (node (ref "U2") (pin "3") (pinfunction "~{CE}_3") (pintype "input"))
      (node (ref "U5") (pin "5") (pinfunction "ST_5") (pintype "output"))
    )
    (net (code "35") (name "Net-(U6-FB)") (class "Default")
      (node (ref "C7") (pin "2") (pinfunction "2_2") (pintype "passive"))
      (node (ref "R4") (pin "1") (pinfunction "1_1") (pintype "passive"))
      (node (ref "R7") (pin "1") (pinfunction "1_1") (pintype "passive"))
      (node (ref "U6") (pin "1") (pinfunction "FB_1") (pintype "passive"))
    )
    (net (code "36") (name "Net-(U6-SW)") (class "Default")
      (node (ref "L2") (pin "2") (pinfunction "2_2") (pintype "passive"))
      (node (ref "U6") (pin "5") (pinfunction "SW_5") (pintype "passive"))
    )
    (net (code "37") (name "VBAT") (class "Default")
      (node (ref "D4") (pin "2") (pinfunction "A_2") (pintype "passive"))
      (node (ref "SW2") (pin "1") (pinfunction "1_1") (pintype "passive"))
    )
    (net (code "38") (name "VBUS") (class "Default")
      (node (ref "C1") (pin "1") (pinfunction "1_1") (pintype "passive"))
      (node (ref "C5") (pin "1") (pinfunction "1_1") (pintype "passive"))
      (node (ref "J1") (pin "1") (pinfunction "VBUS_1") (pintype "passive"))
      (node (ref "L1") (pin "1") (pinfunction "1_1") (pintype "passive"))
      (node (ref "U3") (pin "1") (pinfunction "VCC_1") (pintype "power_in"))
    )
    (net (code "39") (name "VBUS_FILT") (class "Default")
      (node (ref "C2") (pin "1") (pinfunction "1_1") (pintype "passive"))
      (node (ref "C3") (pin "1") (pinfunction "1_1") (pintype "passive"))
      (node (ref "D1") (pin "1") (pinfunction "K_1") (pintype "passive"))
      (node (ref "L1") (pin "2") (pinfunction "2_2") (pintype "passive"))
      (node (ref "Q1") (pin "1") (pinfunction "G_1") (pintype "passive"))
      (node (ref "R3") (pin "1") (pinfunction "1_1") (pintype "passive"))
      (node (ref "U1") (pin "4") (pinfunction "EN_4") (pintype "input"))
      (node (ref "U1") (pin "6") (pinfunction "IN_6") (pintype "power_in"))
    )
    (net (code "40") (name "unconnected-(J1-ID-Pad4)") (class "Default")
      (node (ref "J1") (pin "4") (pinfunction "ID_4") (pintype "passive+no_connect"))
    )
    (net (code "41") (name "unconnected-(J1-SHLD1-Pad6)") (class "Default")
      (node (ref "J1") (pin "6") (pinfunction "SHLD1_6") (pintype "passive+no_connect"))
    )
    (net (code "42") (name "unconnected-(J1-SHLD2-Pad7)") (class "Default")
      (node (ref "J1") (pin "7") (pinfunction "SHLD2_7") (pintype "passive+no_connect"))
    )
    (net (code "43") (name "unconnected-(J1-SHLD3-Pad8)") (class "Default")
      (node (ref "J1") (pin "8") (pinfunction "SHLD3_8") (pintype "passive+no_connect"))
    )
    (net (code "44") (name "unconnected-(J1-SHLD4-Pad9)") (class "Default")
      (node (ref "J1") (pin "9") (pinfunction "SHLD4_9") (pintype "passive+no_connect"))
    )
    (net (code "45") (name "unconnected-(J1-SHLD5-Pad10)") (class "Default")
      (node (ref "J1") (pin "10") (pinfunction "SHLD5_10") (pintype "passive+no_connect"))
    )
    (net (code "46") (name "unconnected-(J1-SHLD6-Pad11)") (class "Default")
      (node (ref "J1") (pin "11") (pinfunction "SHLD6_11") (pintype "passive+no_connect"))
    )
    (net (code "47") (name "unconnected-(MD1-NC-Pad4)") (class "Default")
      (node (ref "MD1") (pin "4") (pinfunction "NC_4") (pintype "passive+no_connect"))
    )
    (net (code "48") (name "unconnected-(MD1-NC-Pad7)") (class "Default")
      (node (ref "MD1") (pin "7") (pinfunction "NC_7") (pintype "passive+no_connect"))
    )
    (net (code "49") (name "unconnected-(MD1-NC-Pad9)") (class "Default")
      (node (ref "MD1") (pin "9") (pinfunction "NC_9") (pintype "passive+no_connect"))
    )
    (net (code "50") (name "unconnected-(MD1-NC-Pad10)") (class "Default")
      (node (ref "MD1") (pin "10") (pinfunction "NC_10") (pintype "passive+no_connect"))
    )
    (net (code "51") (name "unconnected-(MD1-NC-Pad15)") (class "Default")
      (node (ref "MD1") (pin "15") (pinfunction "NC_15") (pintype "passive+no_connect"))
    )
    (net (code "52") (name "unconnected-(MD1-NC-Pad17)") (class "Default")
      (node (ref "MD1") (pin "17") (pinfunction "NC_17") (pintype "passive+no_connect"))
    )
    (net (code "53") (name "unconnected-(MD1-NC-Pad24)") (class "Default")
      (node (ref "MD1") (pin "24") (pinfunction "NC_24") (pintype "passive+no_connect"))
    )
    (net (code "54") (name "unconnected-(MD1-NC-Pad25)") (class "Default")
      (node (ref "MD1") (pin "25") (pinfunction "NC_25") (pintype "passive+no_connect"))
    )
    (net (code "55") (name "unconnected-(MD1-NC-Pad28)") (class "Default")
      (node (ref "MD1") (pin "28") (pinfunction "NC_28") (pintype "passive+no_connect"))
    )
    (net (code "56") (name "unconnected-(MD1-NC-Pad29)") (class "Default")
      (node (ref "MD1") (pin "29") (pinfunction "NC_29") (pintype "passive+no_connect"))
    )
    (net (code "57") (name "unconnected-(MD1-NC-Pad32)") (class "Default")
      (node (ref "MD1") (pin "32") (pinfunction "NC_32") (pintype "passive+no_connect"))
    )
    (net (code "58") (name "unconnected-(MD1-NC-Pad33)") (class "Default")
      (node (ref "MD1") (pin "33") (pinfunction "NC_33") (pintype "passive+no_connect"))
    )
    (net (code "59") (name "unconnected-(MD1-NC-Pad34)") (class "Default")
      (node (ref "MD1") (pin "34") (pinfunction "NC_34") (pintype "passive+no_connect"))
    )
    (net (code "60") (name "unconnected-(MD1-NC-Pad35)") (class "Default")
      (node (ref "MD1") (pin "35") (pinfunction "NC_35") (pintype "passive+no_connect"))
    )
    (net (code "61") (name "unconnected-(R12-Pad1)") (class "Default")
      (node (ref "R12") (pin "1") (pinfunction "1_1") (pintype "passive"))
    )
    (net (code "62") (name "unconnected-(R13-Pad3)") (class "Default")
      (node (ref "R13") (pin "3") (pinfunction "3_3") (pintype "passive"))
    )
    (net (code "63") (name "unconnected-(R14-Pad3)") (class "Default")
      (node (ref "R14") (pin "3") (pinfunction "3_3") (pintype "passive"))
    )
    (net (code "64") (name "unconnected-(R15-Pad1)") (class "Default")
      (node (ref "R15") (pin "1") (pinfunction "1_1") (pintype "passive"))
    )
    (net (code "65") (name "unconnected-(U2-NC-Pad4)") (class "Default")
      (node (ref "U2") (pin "4") (pinfunction "NC_4") (pintype "passive+no_connect"))
    )
    (net (code "66") (name "unconnected-(U3-NC-Pad2)") (class "Default")
      (node (ref "U3") (pin "2") (pinfunction "NC_2") (pintype "passive+no_connect"))
    )
    (net (code "67") (name "unconnected-(U4-NC-Pad2)") (class "Default")
      (node (ref "U4") (pin "2") (pinfunction "NC_2") (pintype "passive+no_connect"))
    )
    (net (code "68") (name "unconnected-(U5-NC-Pad4)") (class "Default")
      (node (ref "U5") (pin "4") (pinfunction "NC_4") (pintype "passive+no_connect"))
    )
    (net (code "69") (name "unconnected-(U7B-GND-Pad11)") (class "Default")
      (node (ref "U7") (pin "11") (pinfunction "GND_11") (pintype "power_in"))
    )
    (net (code "70") (name "unconnected-(U7B-VDD-Pad4)") (class "Default")
      (node (ref "U7") (pin "4") (pinfunction "VDD_4") (pintype "power_in"))
    )
    (net (code "71") (name "unconnected-(U7C-GND-Pad11)") (class "Default")
      (node (ref "U7") (pin "11") (pinfunction "GND_11") (pintype "power_in"))
    )
    (net (code "72") (name "unconnected-(U7C-VDD-Pad4)") (class "Default")
      (node (ref "U7") (pin "4") (pinfunction "VDD_4") (pintype "power_in"))
    )
    (net (code "73") (name "unconnected-(U7D-GND-Pad11)") (class "Default")
      (node (ref "U7") (pin "11") (pinfunction "GND_11") (pintype "power_in"))
    )
    (net (code "74") (name "unconnected-(U7D-VDD-Pad4)") (class "Default")
      (node (ref "U7") (pin "4") (pinfunction "VDD_4") (pintype "power_in"))
    )
  )
)
